# controller7connector.net
KiCad netlist of a schematic drawn in EAGLE
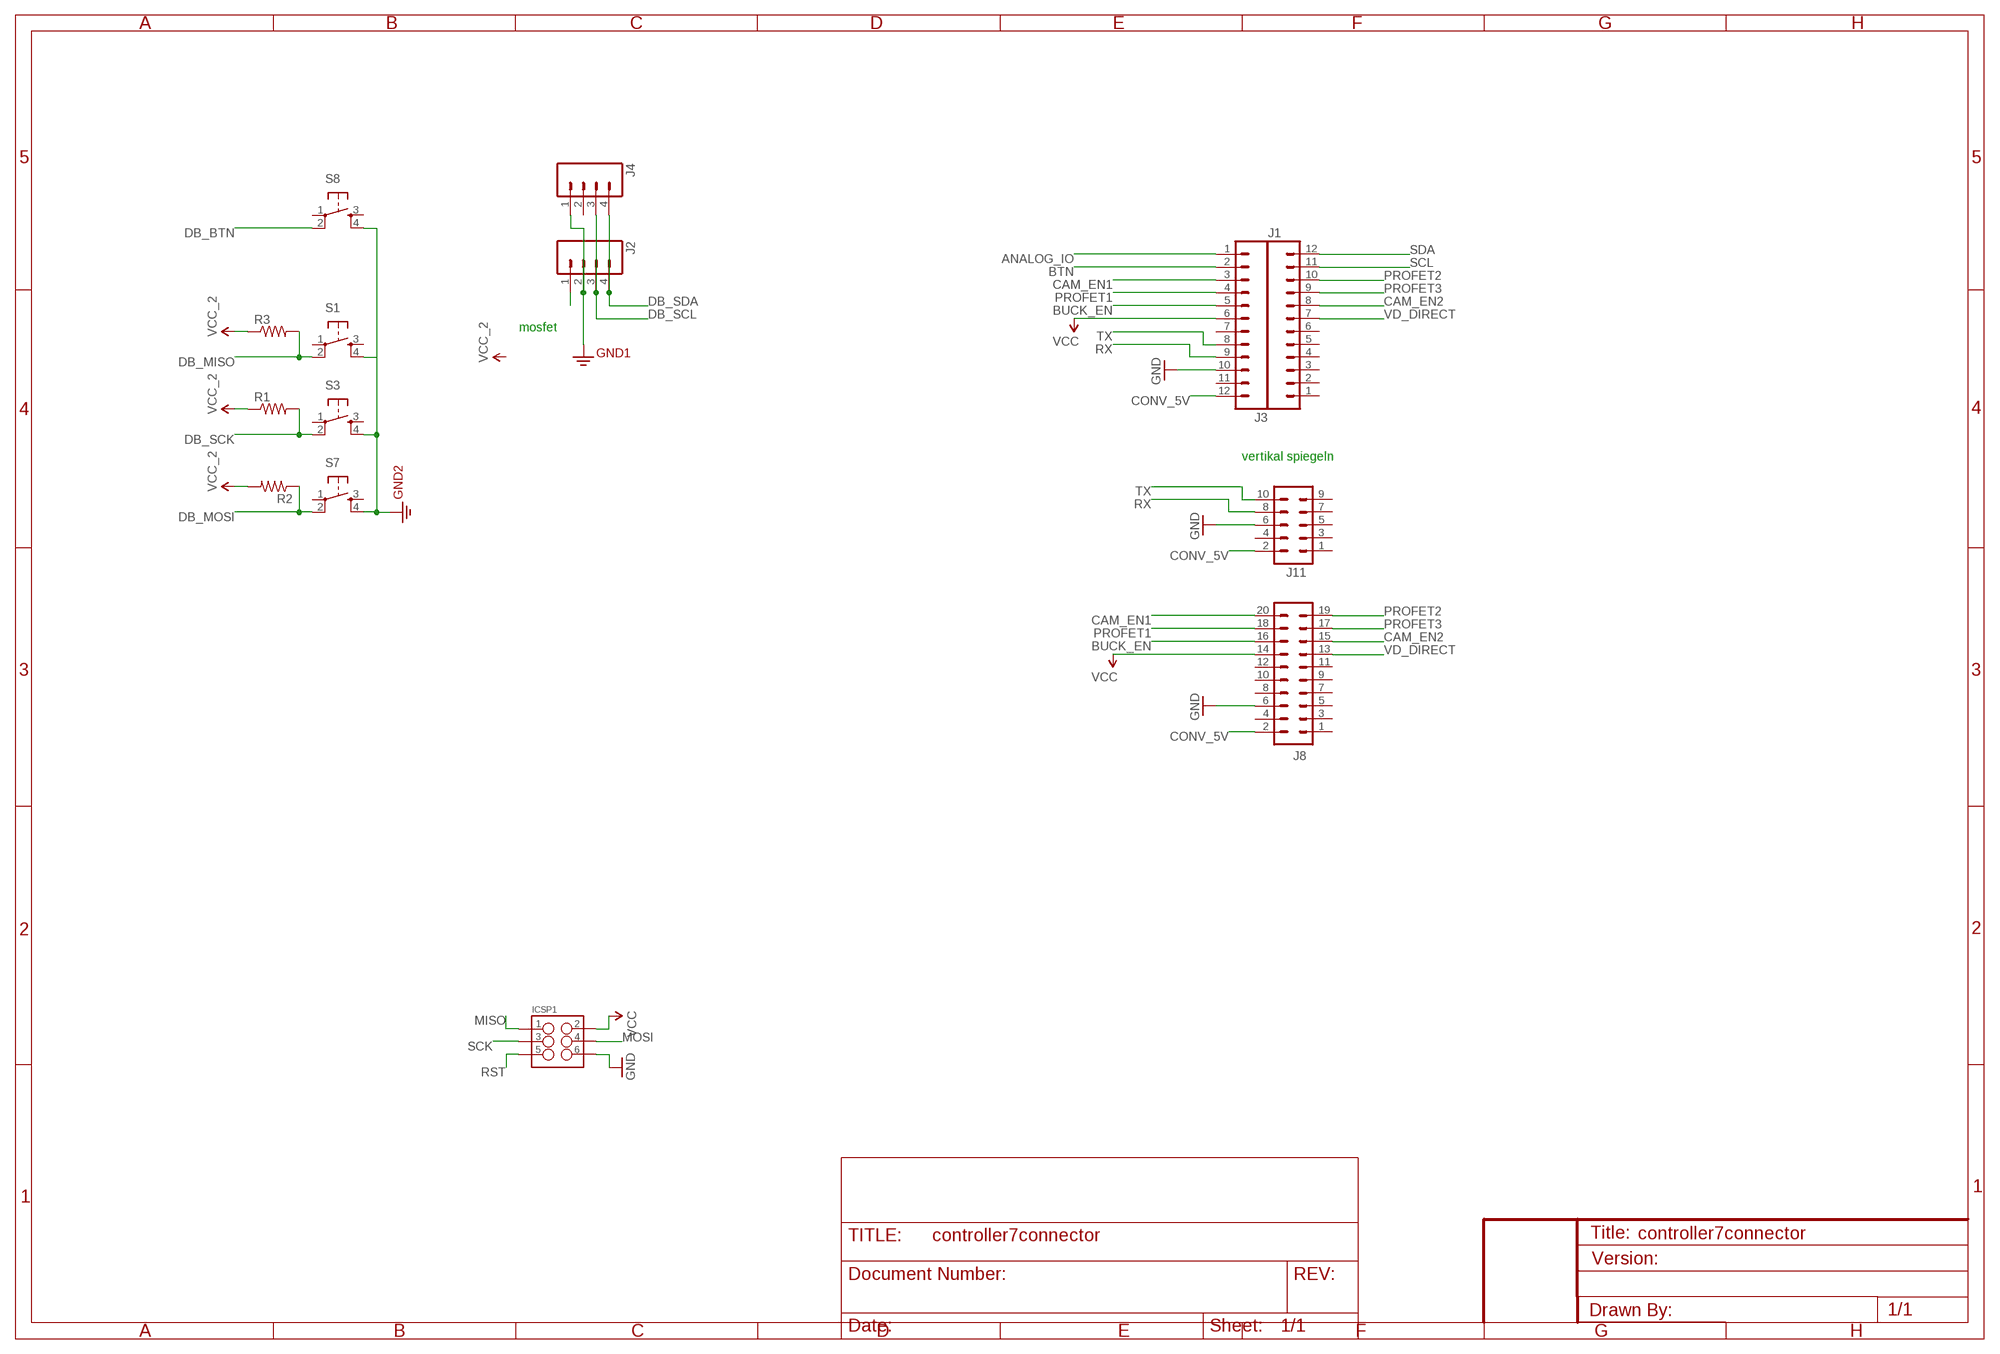
[diagram p0: schematic, sheet 1]

(export (version "E")
  (design (tool "Eeschema 10.0.6"))
  (components
    (comp (ref "ICSP1")
      (value "M03X2FEMALE")
      (footprint "eagle-import:2X3")
      (libsource (lib "eagle-import") (part "M03X2FEMALE"))
    )
    (comp (ref "J1")
      (value "M12PTH")
      (footprint "eagle-import:1X12")
      (libsource (lib "eagle-import") (part "M12PTH"))
    )
    (comp (ref "J2")
      (value "M04LOCK")
      (footprint "eagle-import:1X04_LOCK")
      (libsource (lib "eagle-import") (part "M04LOCK"))
    )
    (comp (ref "J3")
      (value "M12PTH")
      (footprint "eagle-import:1X12")
      (libsource (lib "eagle-import") (part "M12PTH"))
    )
    (comp (ref "J4")
      (value "M04LOCK")
      (footprint "eagle-import:1X04_LOCK")
      (libsource (lib "eagle-import") (part "M04LOCK"))
    )
    (comp (ref "J8")
      (value "M10X2")
      (footprint "eagle-import:2X10")
      (libsource (lib "eagle-import") (part "M10X2"))
    )
    (comp (ref "J11")
      (value "M05X2NO_SILK")
      (footprint "eagle-import:2X5_NOSILK")
      (libsource (lib "eagle-import") (part "M05X2NO_SILK"))
    )
    (comp (ref "R1")
      (value "RESISTOR1206")
      (footprint "eagle-import:1206")
      (libsource (lib "eagle-import") (part "RESISTOR1206"))
    )
    (comp (ref "R2")
      (value "RESISTOR1206")
      (footprint "eagle-import:1206")
      (libsource (lib "eagle-import") (part "RESISTOR1206"))
    )
    (comp (ref "R3")
      (value "RESISTOR1206")
      (footprint "eagle-import:1206")
      (libsource (lib "eagle-import") (part "RESISTOR1206"))
    )
    (comp (ref "S1")
      (value "TAC_SWITCHPTH")
      (footprint "eagle-import:TACTILE-PTH")
      (libsource (lib "eagle-import") (part "TAC_SWITCHPTH"))
    )
    (comp (ref "S3")
      (value "TAC_SWITCHPTH")
      (footprint "eagle-import:TACTILE-PTH")
      (libsource (lib "eagle-import") (part "TAC_SWITCHPTH"))
    )
    (comp (ref "S7")
      (value "TAC_SWITCHPTH")
      (footprint "eagle-import:TACTILE-PTH")
      (libsource (lib "eagle-import") (part "TAC_SWITCHPTH"))
    )
    (comp (ref "S8")
      (value "TAC_SWITCHPTH")
      (footprint "eagle-import:TACTILE-PTH")
      (libsource (lib "eagle-import") (part "TAC_SWITCHPTH"))
    )
  )
  (nets
    (net (code "1") (name "/ANALOG_IO") (class "Default")
      (node (ref "J3") (pin "1") (pinfunction "1_1") (pintype "passive"))
    )
    (net (code "2") (name "/BTN") (class "Default")
      (node (ref "J3") (pin "2") (pinfunction "2_2") (pintype "passive"))
    )
    (net (code "3") (name "/BUCK_EN") (class "Default")
      (node (ref "J3") (pin "5") (pinfunction "5_5") (pintype "passive"))
      (node (ref "J8") (pin "16") (pinfunction "16_16") (pintype "passive"))
    )
    (net (code "4") (name "/CAM_EN1") (class "Default")
      (node (ref "J3") (pin "3") (pinfunction "3_3") (pintype "passive"))
      (node (ref "J8") (pin "20") (pinfunction "20_20") (pintype "passive"))
    )
    (net (code "5") (name "/CAM_EN2") (class "Default")
      (node (ref "J1") (pin "8") (pinfunction "8_8") (pintype "passive"))
      (node (ref "J8") (pin "15") (pinfunction "15_15") (pintype "passive"))
    )
    (net (code "6") (name "/CONV_5V") (class "Default")
      (node (ref "J11") (pin "2") (pinfunction "2_2") (pintype "passive"))
      (node (ref "J3") (pin "12") (pinfunction "12_12") (pintype "passive"))
      (node (ref "J8") (pin "2") (pinfunction "2_2") (pintype "passive"))
    )
    (net (code "7") (name "/DB_BTN") (class "Default")
      (node (ref "S8") (pin "2") (pinfunction "2_2") (pintype "passive"))
    )
    (net (code "8") (name "/DB_MISO") (class "Default")
      (node (ref "R3") (pin "2") (pinfunction "2_2") (pintype "passive"))
      (node (ref "S1") (pin "2") (pinfunction "2_2") (pintype "passive"))
    )
    (net (code "9") (name "/DB_MOSI") (class "Default")
      (node (ref "R2") (pin "1") (pinfunction "1_1") (pintype "passive"))
      (node (ref "S7") (pin "2") (pinfunction "2_2") (pintype "passive"))
    )
    (net (code "10") (name "/DB_SCK") (class "Default")
      (node (ref "R1") (pin "2") (pinfunction "2_2") (pintype "passive"))
      (node (ref "S3") (pin "2") (pinfunction "2_2") (pintype "passive"))
    )
    (net (code "11") (name "/DB_SCL") (class "Default")
      (node (ref "J2") (pin "3") (pinfunction "3_3") (pintype "passive"))
      (node (ref "J4") (pin "3") (pinfunction "3_3") (pintype "passive"))
    )
    (net (code "12") (name "/DB_SDA") (class "Default")
      (node (ref "J2") (pin "4") (pinfunction "4_4") (pintype "passive"))
      (node (ref "J4") (pin "4") (pinfunction "4_4") (pintype "passive"))
    )
    (net (code "13") (name "/MISO") (class "Default")
      (node (ref "ICSP1") (pin "1") (pinfunction "1_1") (pintype "bidirectional"))
    )
    (net (code "14") (name "/MOSI") (class "Default")
      (node (ref "ICSP1") (pin "4") (pinfunction "4_4") (pintype "bidirectional"))
    )
    (net (code "15") (name "/PROFET1") (class "Default")
      (node (ref "J3") (pin "4") (pinfunction "4_4") (pintype "passive"))
      (node (ref "J8") (pin "18") (pinfunction "18_18") (pintype "passive"))
    )
    (net (code "16") (name "/PROFET2") (class "Default")
      (node (ref "J1") (pin "10") (pinfunction "10_10") (pintype "passive"))
      (node (ref "J8") (pin "19") (pinfunction "19_19") (pintype "passive"))
    )
    (net (code "17") (name "/PROFET3") (class "Default")
      (node (ref "J1") (pin "9") (pinfunction "9_9") (pintype "passive"))
      (node (ref "J8") (pin "17") (pinfunction "17_17") (pintype "passive"))
    )
    (net (code "18") (name "/RST") (class "Default")
      (node (ref "ICSP1") (pin "5") (pinfunction "5_5") (pintype "bidirectional"))
    )
    (net (code "19") (name "/RX") (class "Default")
      (node (ref "J11") (pin "8") (pinfunction "8_8") (pintype "passive"))
      (node (ref "J3") (pin "9") (pinfunction "9_9") (pintype "passive"))
    )
    (net (code "20") (name "/SCK") (class "Default")
      (node (ref "ICSP1") (pin "3") (pinfunction "3_3") (pintype "bidirectional"))
    )
    (net (code "21") (name "/SCL") (class "Default")
      (node (ref "J1") (pin "11") (pinfunction "11_11") (pintype "passive"))
    )
    (net (code "22") (name "/SDA") (class "Default")
      (node (ref "J1") (pin "12") (pinfunction "12_12") (pintype "passive"))
    )
    (net (code "23") (name "/TX") (class "Default")
      (node (ref "J11") (pin "10") (pinfunction "10_10") (pintype "passive"))
      (node (ref "J3") (pin "8") (pinfunction "8_8") (pintype "passive"))
    )
    (net (code "24") (name "/VD_DIRECT") (class "Default")
      (node (ref "J1") (pin "7") (pinfunction "7_7") (pintype "passive"))
      (node (ref "J8") (pin "13") (pinfunction "13_13") (pintype "passive"))
    )
    (net (code "25") (name "GND") (class "Default")
      (node (ref "ICSP1") (pin "6") (pinfunction "6_6") (pintype "bidirectional"))
      (node (ref "J11") (pin "6") (pinfunction "6_6") (pintype "passive"))
      (node (ref "J3") (pin "10") (pinfunction "10_10") (pintype "passive"))
      (node (ref "J8") (pin "6") (pinfunction "6_6") (pintype "passive"))
    )
    (net (code "26") (name "GND2") (class "Default")
      (node (ref "J2") (pin "2") (pinfunction "2_2") (pintype "passive"))
      (node (ref "J4") (pin "1") (pinfunction "1_1") (pintype "passive"))
      (node (ref "S1") (pin "4") (pinfunction "4_4") (pintype "passive"))
      (node (ref "S3") (pin "4") (pinfunction "4_4") (pintype "passive"))
      (node (ref "S7") (pin "4") (pinfunction "4_4") (pintype "passive"))
      (node (ref "S8") (pin "4") (pinfunction "4_4") (pintype "passive"))
    )
    (net (code "27") (name "VCC") (class "Default")
      (node (ref "ICSP1") (pin "2") (pinfunction "2_2") (pintype "bidirectional"))
      (node (ref "J3") (pin "6") (pinfunction "6_6") (pintype "passive"))
      (node (ref "J8") (pin "14") (pinfunction "14_14") (pintype "passive"))
    )
    (net (code "28") (name "VCC_2") (class "Default")
      (node (ref "R1") (pin "1") (pinfunction "1_1") (pintype "passive"))
      (node (ref "R2") (pin "2") (pinfunction "2_2") (pintype "passive"))
      (node (ref "R3") (pin "1") (pinfunction "1_1") (pintype "passive"))
    )
    (net (code "29") (name "unconnected-(J1-Pad1)") (class "Default")
      (node (ref "J1") (pin "1") (pinfunction "1_1") (pintype "passive"))
    )
    (net (code "30") (name "unconnected-(J1-Pad2)") (class "Default")
      (node (ref "J1") (pin "2") (pinfunction "2_2") (pintype "passive"))
    )
    (net (code "31") (name "unconnected-(J1-Pad3)") (class "Default")
      (node (ref "J1") (pin "3") (pinfunction "3_3") (pintype "passive"))
    )
    (net (code "32") (name "unconnected-(J1-Pad4)") (class "Default")
      (node (ref "J1") (pin "4") (pinfunction "4_4") (pintype "passive"))
    )
    (net (code "33") (name "unconnected-(J1-Pad5)") (class "Default")
      (node (ref "J1") (pin "5") (pinfunction "5_5") (pintype "passive"))
    )
    (net (code "34") (name "unconnected-(J1-Pad6)") (class "Default")
      (node (ref "J1") (pin "6") (pinfunction "6_6") (pintype "passive"))
    )
    (net (code "35") (name "unconnected-(J2-Pad1)") (class "Default")
      (node (ref "J2") (pin "1") (pinfunction "1_1") (pintype "passive"))
    )
    (net (code "36") (name "unconnected-(J3-Pad7)") (class "Default")
      (node (ref "J3") (pin "7") (pinfunction "7_7") (pintype "passive"))
    )
    (net (code "37") (name "unconnected-(J3-Pad11)") (class "Default")
      (node (ref "J3") (pin "11") (pinfunction "11_11") (pintype "passive"))
    )
    (net (code "38") (name "unconnected-(J4-Pad2)") (class "Default")
      (node (ref "J4") (pin "2") (pinfunction "2_2") (pintype "passive"))
    )
    (net (code "39") (name "unconnected-(J8-Pad1)") (class "Default")
      (node (ref "J8") (pin "1") (pinfunction "1_1") (pintype "passive"))
    )
    (net (code "40") (name "unconnected-(J8-Pad3)") (class "Default")
      (node (ref "J8") (pin "3") (pinfunction "3_3") (pintype "passive"))
    )
    (net (code "41") (name "unconnected-(J8-Pad4)") (class "Default")
      (node (ref "J8") (pin "4") (pinfunction "4_4") (pintype "passive"))
    )
    (net (code "42") (name "unconnected-(J8-Pad5)") (class "Default")
      (node (ref "J8") (pin "5") (pinfunction "5_5") (pintype "passive"))
    )
    (net (code "43") (name "unconnected-(J8-Pad7)") (class "Default")
      (node (ref "J8") (pin "7") (pinfunction "7_7") (pintype "passive"))
    )
    (net (code "44") (name "unconnected-(J8-Pad8)") (class "Default")
      (node (ref "J8") (pin "8") (pinfunction "8_8") (pintype "passive"))
    )
    (net (code "45") (name "unconnected-(J8-Pad9)") (class "Default")
      (node (ref "J8") (pin "9") (pinfunction "9_9") (pintype "passive"))
    )
    (net (code "46") (name "unconnected-(J8-Pad10)") (class "Default")
      (node (ref "J8") (pin "10") (pinfunction "10_10") (pintype "passive"))
    )
    (net (code "47") (name "unconnected-(J8-Pad11)") (class "Default")
      (node (ref "J8") (pin "11") (pinfunction "11_11") (pintype "passive"))
    )
    (net (code "48") (name "unconnected-(J8-Pad12)") (class "Default")
      (node (ref "J8") (pin "12") (pinfunction "12_12") (pintype "passive"))
    )
    (net (code "49") (name "unconnected-(J11-Pad1)") (class "Default")
      (node (ref "J11") (pin "1") (pinfunction "1_1") (pintype "passive"))
    )
    (net (code "50") (name "unconnected-(J11-Pad3)") (class "Default")
      (node (ref "J11") (pin "3") (pinfunction "3_3") (pintype "passive"))
    )
    (net (code "51") (name "unconnected-(J11-Pad4)") (class "Default")
      (node (ref "J11") (pin "4") (pinfunction "4_4") (pintype "passive"))
    )
    (net (code "52") (name "unconnected-(J11-Pad5)") (class "Default")
      (node (ref "J11") (pin "5") (pinfunction "5_5") (pintype "passive"))
    )
    (net (code "53") (name "unconnected-(J11-Pad7)") (class "Default")
      (node (ref "J11") (pin "7") (pinfunction "7_7") (pintype "passive"))
    )
    (net (code "54") (name "unconnected-(J11-Pad9)") (class "Default")
      (node (ref "J11") (pin "9") (pinfunction "9_9") (pintype "passive"))
    )
    (net (code "55") (name "unconnected-(S1-Pad1)") (class "Default")
      (node (ref "S1") (pin "1") (pinfunction "1_1") (pintype "passive"))
    )
    (net (code "56") (name "unconnected-(S1-Pad3)") (class "Default")
      (node (ref "S1") (pin "3") (pinfunction "3_3") (pintype "passive"))
    )
    (net (code "57") (name "unconnected-(S3-Pad1)") (class "Default")
      (node (ref "S3") (pin "1") (pinfunction "1_1") (pintype "passive"))
    )
    (net (code "58") (name "unconnected-(S3-Pad3)") (class "Default")
      (node (ref "S3") (pin "3") (pinfunction "3_3") (pintype "passive"))
    )
    (net (code "59") (name "unconnected-(S7-Pad1)") (class "Default")
      (node (ref "S7") (pin "1") (pinfunction "1_1") (pintype "passive"))
    )
    (net (code "60") (name "unconnected-(S7-Pad3)") (class "Default")
      (node (ref "S7") (pin "3") (pinfunction "3_3") (pintype "passive"))
    )
    (net (code "61") (name "unconnected-(S8-Pad1)") (class "Default")
      (node (ref "S8") (pin "1") (pinfunction "1_1") (pintype "passive"))
    )
    (net (code "62") (name "unconnected-(S8-Pad3)") (class "Default")
      (node (ref "S8") (pin "3") (pinfunction "3_3") (pintype "passive"))
    )
  )
)
